# meroTV.net
KiCad netlist of a schematic drawn in EAGLE
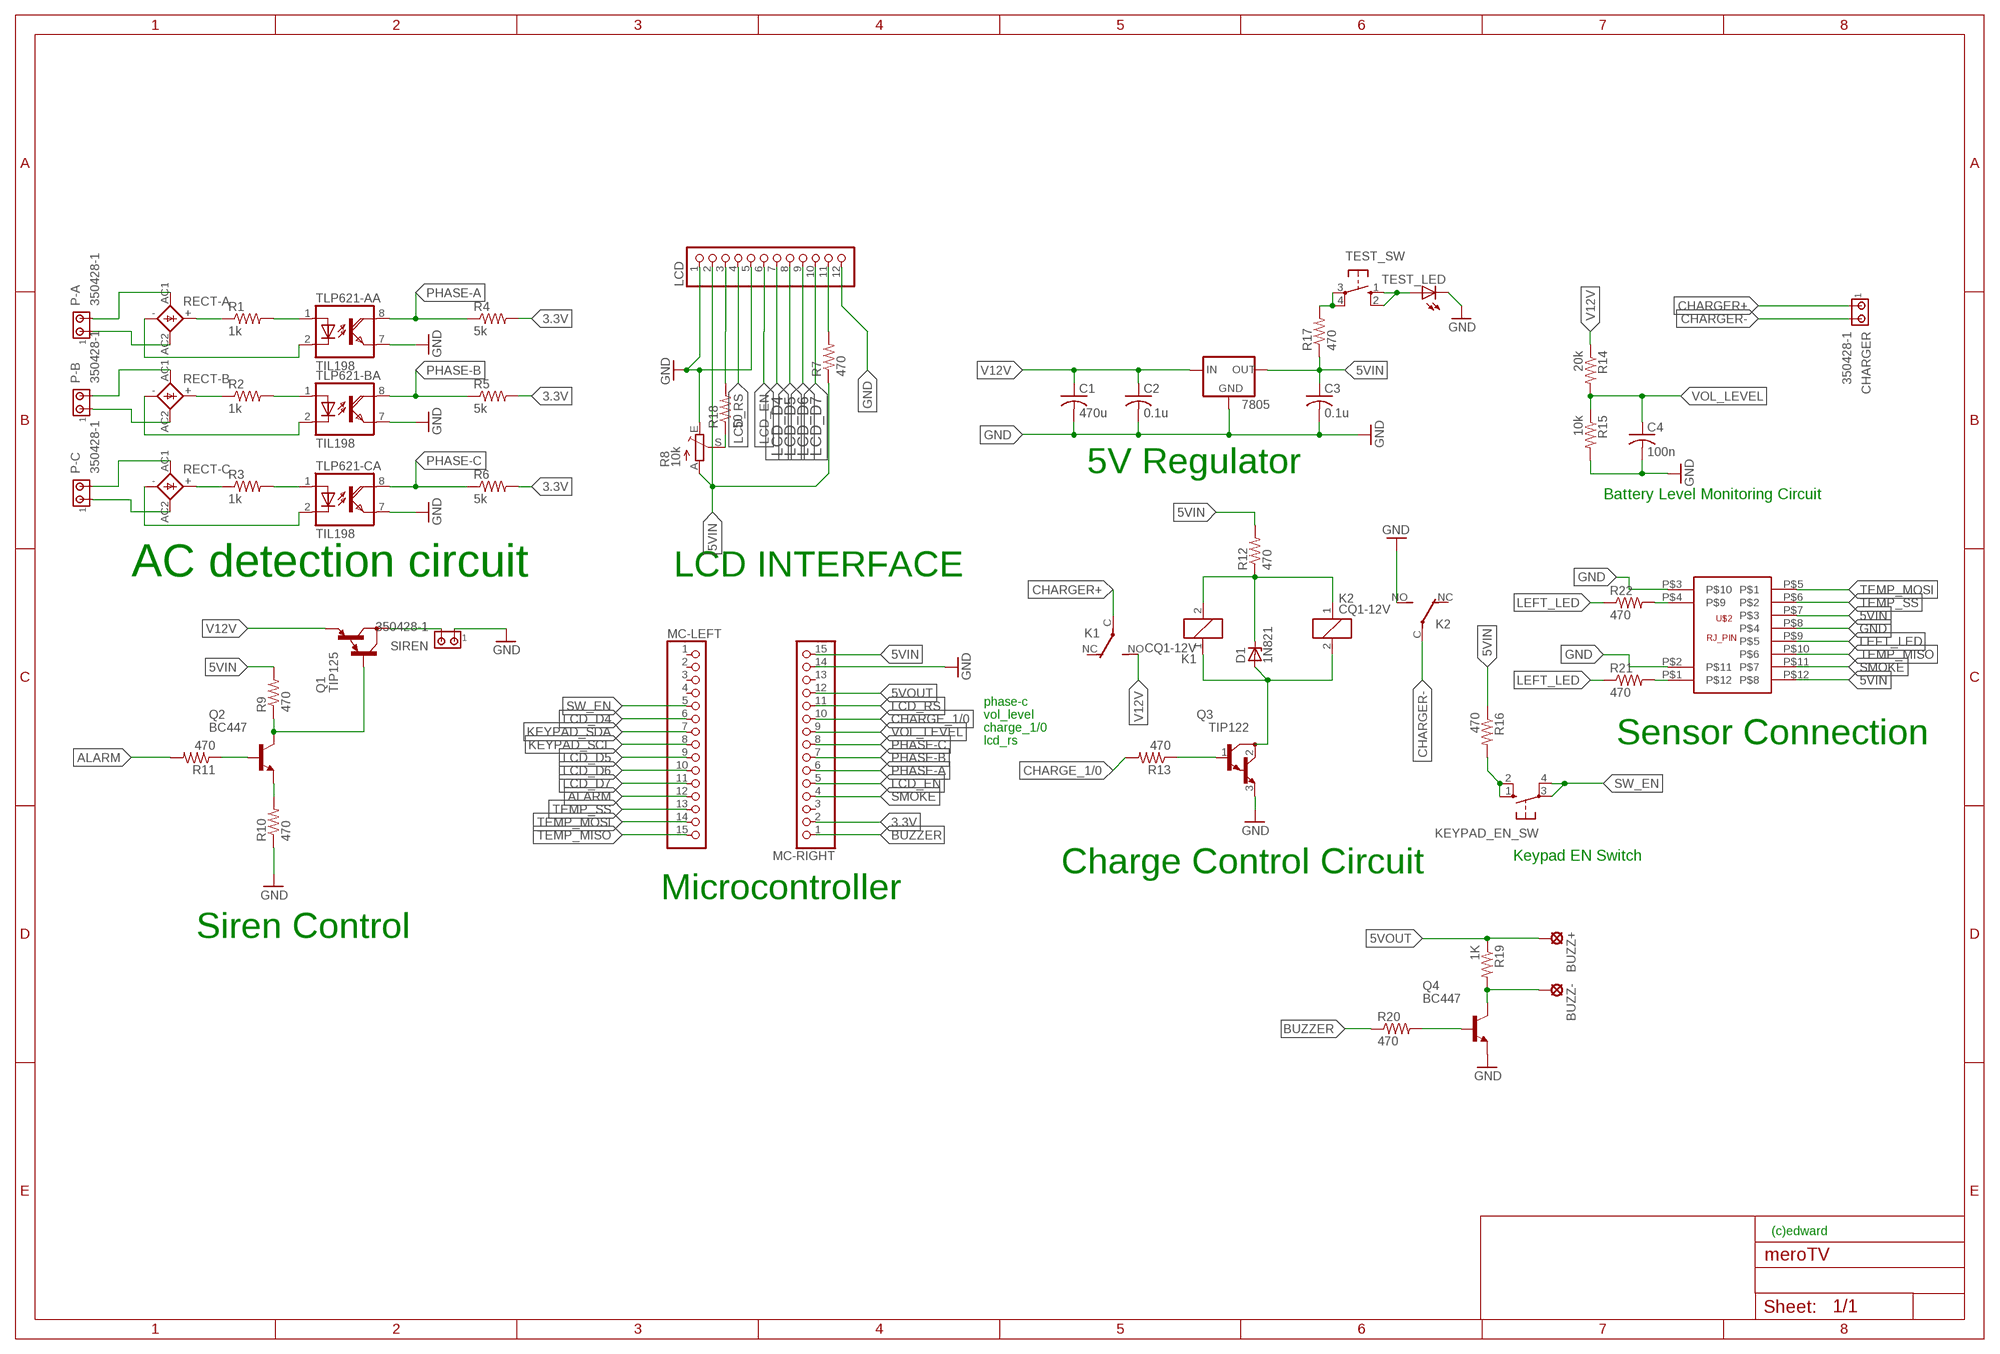
[diagram p0: schematic, sheet 1]

(export (version "E")
  (design (tool "Eeschema 10.0.6"))
  (components
    (comp (ref "7805")
      (value "78MXXL")
      (footprint "eagle-import:78MXXL")
      (libsource (lib "eagle-import") (part "78MXXL"))
    )
    (comp (ref "BUZZ+")
      (value "SE11")
      (footprint "eagle-import:SE11")
      (libsource (lib "eagle-import") (part "SE11"))
    )
    (comp (ref "BUZZ-")
      (value "SE11")
      (footprint "eagle-import:SE11")
      (libsource (lib "eagle-import") (part "SE11"))
    )
    (comp (ref "C1")
      (value "470u")
      (footprint "eagle-import:C025-040X050")
      (libsource (lib "eagle-import") (part "C-US025-040X050"))
    )
    (comp (ref "C2")
      (value "0.1u")
      (footprint "eagle-import:C025-030X050")
      (libsource (lib "eagle-import") (part "C-US025-030X050"))
    )
    (comp (ref "C3")
      (value "0.1u")
      (footprint "eagle-import:C025-030X050")
      (libsource (lib "eagle-import") (part "C-US025-030X050"))
    )
    (comp (ref "C4")
      (value "100n")
      (footprint "eagle-import:C025-030X050")
      (libsource (lib "eagle-import") (part "C-US025-030X050"))
    )
    (comp (ref "CHARGER")
      (value "350428-1")
      (footprint "eagle-import:350428-1")
      (libsource (lib "eagle-import") (part "350428-1"))
    )
    (comp (ref "D1")
      (value "1N821")
      (footprint "eagle-import:DO35Z10")
      (libsource (lib "eagle-import") (part "1N821"))
    )
    (comp (ref "K1")
      (value "CQ1-12V")
      (footprint "eagle-import:CQ1")
      (libsource (lib "eagle-import") (part "CQ1-12V"))
    )
    (comp (ref "K2")
      (value "CQ1-12V")
      (footprint "eagle-import:CQ1")
      (libsource (lib "eagle-import") (part "CQ1-12V"))
    )
    (comp (ref "KEYPAD_EN_SW")
      (value "10-XX")
      (footprint "eagle-import:B3F-10XX")
      (fields (field (name "MPN") "B3F-1000"))
      (libsource (lib "eagle-import") (part "10-XX"))
    )
    (comp (ref "LCD")
      (value "PINHD-1X12")
      (footprint "eagle-import:1X12")
      (libsource (lib "eagle-import") (part "PINHD-1X12"))
    )
    (comp (ref "MC-LEFT")
      (value "PINHD-1X15")
      (footprint "eagle-import:1X15")
      (libsource (lib "eagle-import") (part "PINHD-1X15"))
    )
    (comp (ref "MC-RIGHT")
      (value "PINHD-1X15")
      (footprint "eagle-import:1X15")
      (libsource (lib "eagle-import") (part "PINHD-1X15"))
    )
    (comp (ref "P-A")
      (value "350428-1")
      (footprint "eagle-import:350428-1")
      (libsource (lib "eagle-import") (part "350428-1"))
    )
    (comp (ref "P-B")
      (value "350428-1")
      (footprint "eagle-import:350428-1")
      (libsource (lib "eagle-import") (part "350428-1"))
    )
    (comp (ref "P-C")
      (value "350428-1")
      (footprint "eagle-import:350428-1")
      (libsource (lib "eagle-import") (part "350428-1"))
    )
    (comp (ref "Q1")
      (value "TIP125")
      (footprint "eagle-import:TO220")
      (libsource (lib "eagle-import") (part "TIP125"))
    )
    (comp (ref "Q2")
      (value "BC447")
      (footprint "eagle-import:TO92-EBC")
      (libsource (lib "eagle-import") (part "BC447"))
    )
    (comp (ref "Q3")
      (value "TIP122")
      (footprint "eagle-import:TO220")
      (libsource (lib "eagle-import") (part "TIP122"))
    )
    (comp (ref "Q4")
      (value "BC447")
      (footprint "eagle-import:TO92-EBC")
      (libsource (lib "eagle-import") (part "BC447"))
    )
    (comp (ref "R1")
      (value "1k")
      (footprint "eagle-import:0204_5")
      (libsource (lib "eagle-import") (part "R-US_0204/5"))
    )
    (comp (ref "R2")
      (value "1k")
      (footprint "eagle-import:0204_5")
      (libsource (lib "eagle-import") (part "R-US_0204/5"))
    )
    (comp (ref "R3")
      (value "1k")
      (footprint "eagle-import:0204_5")
      (libsource (lib "eagle-import") (part "R-US_0204/5"))
    )
    (comp (ref "R4")
      (value "5k")
      (footprint "eagle-import:0204_5")
      (libsource (lib "eagle-import") (part "R-US_0204/5"))
    )
    (comp (ref "R5")
      (value "5k")
      (footprint "eagle-import:0204_5")
      (libsource (lib "eagle-import") (part "R-US_0204/5"))
    )
    (comp (ref "R6")
      (value "5k")
      (footprint "eagle-import:0204_5")
      (libsource (lib "eagle-import") (part "R-US_0204/5"))
    )
    (comp (ref "R7")
      (value "470")
      (footprint "eagle-import:0204_5")
      (libsource (lib "eagle-import") (part "R-US_0204/5"))
    )
    (comp (ref "R8")
      (value "10k")
      (footprint "eagle-import:B25V")
      (libsource (lib "eagle-import") (part "TRIM_EU-B25V"))
    )
    (comp (ref "R9")
      (value "470")
      (footprint "eagle-import:0204_5")
      (libsource (lib "eagle-import") (part "R-US_0204/5"))
    )
    (comp (ref "R10")
      (value "470")
      (footprint "eagle-import:0204_5")
      (libsource (lib "eagle-import") (part "R-US_0204/5"))
    )
    (comp (ref "R11")
      (value "470")
      (footprint "eagle-import:0204_5")
      (libsource (lib "eagle-import") (part "R-US_0204/5"))
    )
    (comp (ref "R12")
      (value "470")
      (footprint "eagle-import:0204_5")
      (libsource (lib "eagle-import") (part "R-US_0204/5"))
    )
    (comp (ref "R13")
      (value "470")
      (footprint "eagle-import:0204_5")
      (libsource (lib "eagle-import") (part "R-US_0204/5"))
    )
    (comp (ref "R14")
      (value "20k")
      (footprint "eagle-import:0204_5")
      (libsource (lib "eagle-import") (part "R-US_0204/5"))
    )
    (comp (ref "R15")
      (value "10k")
      (footprint "eagle-import:0204_5")
      (libsource (lib "eagle-import") (part "R-US_0204/5"))
    )
    (comp (ref "R16")
      (value "470")
      (footprint "eagle-import:0204_5")
      (libsource (lib "eagle-import") (part "R-US_0204/5"))
    )
    (comp (ref "R17")
      (value "470")
      (footprint "eagle-import:0204_5")
      (libsource (lib "eagle-import") (part "R-US_0204/5"))
    )
    (comp (ref "R18")
      (value "50")
      (footprint "eagle-import:0204_5")
      (libsource (lib "eagle-import") (part "R-US_0204/5"))
    )
    (comp (ref "R19")
      (value "1K")
      (footprint "eagle-import:0204_5")
      (libsource (lib "eagle-import") (part "R-US_0204/5"))
    )
    (comp (ref "R20")
      (value "470")
      (footprint "eagle-import:0204_5")
      (libsource (lib "eagle-import") (part "R-US_0204/5"))
    )
    (comp (ref "R21")
      (value "470")
      (footprint "eagle-import:0204_5")
      (libsource (lib "eagle-import") (part "R-US_0204/5"))
    )
    (comp (ref "R22")
      (value "470")
      (footprint "eagle-import:0204_5")
      (libsource (lib "eagle-import") (part "R-US_0204/5"))
    )
    (comp (ref "RECT-A")
      (value "2KBB-R")
      (footprint "eagle-import:2KBB-R")
      (libsource (lib "eagle-import") (part "2KBB-R"))
    )
    (comp (ref "RECT-B")
      (value "2KBB-R")
      (footprint "eagle-import:2KBB-R")
      (libsource (lib "eagle-import") (part "2KBB-R"))
    )
    (comp (ref "RECT-C")
      (value "2KBB-R")
      (footprint "eagle-import:2KBB-R")
      (libsource (lib "eagle-import") (part "2KBB-R"))
    )
    (comp (ref "SIREN")
      (value "350428-1")
      (footprint "eagle-import:350428-1")
      (libsource (lib "eagle-import") (part "350428-1"))
    )
    (comp (ref "TEST_LED")
      (value "LED3MM")
      (footprint "eagle-import:LED3MM")
      (libsource (lib "eagle-import") (part "LED3MM"))
    )
    (comp (ref "TEST_SW")
      (value "10-XX")
      (footprint "eagle-import:B3F-10XX")
      (fields (field (name "MPN") "B3F-1000"))
      (libsource (lib "eagle-import") (part "10-XX"))
    )
    (comp (ref "TLP621-A")
      (value "TIL198")
      (footprint "eagle-import:DIL08")
      (libsource (lib "eagle-import") (part "TIL198"))
    )
    (comp (ref "TLP621-B")
      (value "TIL198")
      (footprint "eagle-import:DIL08")
      (libsource (lib "eagle-import") (part "TIL198"))
    )
    (comp (ref "TLP621-C")
      (value "TIL198")
      (footprint "eagle-import:DIL08")
      (libsource (lib "eagle-import") (part "TIL198"))
    )
    (comp (ref "U$2")
      (value "RJ45_EDWRJ45-DIL")
      (footprint "eagle-import:RJ45-DIL")
      (libsource (lib "eagle-import") (part "RJ45_EDWRJ45-DIL"))
    )
  )
  (nets
    (net (code "1") (name "3.3V") (class "Default")
      (node (ref "MC-RIGHT") (pin "2") (pinfunction "2_2") (pintype "passive"))
      (node (ref "R4") (pin "2") (pinfunction "2_2") (pintype "passive"))
      (node (ref "R5") (pin "2") (pinfunction "2_2") (pintype "passive"))
      (node (ref "R6") (pin "2") (pinfunction "2_2") (pintype "passive"))
    )
    (net (code "2") (name "5VIN") (class "Default")
      (node (ref "7805") (pin "OUT") (pinfunction "OUT_OUT") (pintype "passive"))
      (node (ref "C3") (pin "1") (pinfunction "1_1") (pintype "passive"))
      (node (ref "LCD") (pin "2") (pinfunction "2_2") (pintype "passive"))
      (node (ref "MC-RIGHT") (pin "15") (pinfunction "15_15") (pintype "passive"))
      (node (ref "R12") (pin "2") (pinfunction "2_2") (pintype "passive"))
      (node (ref "R16") (pin "1") (pinfunction "1_1") (pintype "passive"))
      (node (ref "R17") (pin "1") (pinfunction "1_1") (pintype "passive"))
      (node (ref "R7") (pin "1") (pinfunction "1_1") (pintype "passive"))
      (node (ref "R8") (pin "A") (pinfunction "A_A") (pintype "passive"))
      (node (ref "R9") (pin "2") (pinfunction "2_2") (pintype "passive"))
      (node (ref "U$2") (pin "P$12") (pinfunction "P$8_P$12") (pintype "bidirectional"))
      (node (ref "U$2") (pin "P$7") (pinfunction "P$3_P$7") (pintype "bidirectional"))
    )
    (net (code "3") (name "5VOUT") (class "Default")
      (node (ref "BUZZ+") (pin "MP") (pinfunction "MP_MP") (pintype "passive"))
      (node (ref "MC-RIGHT") (pin "12") (pinfunction "12_12") (pintype "passive"))
      (node (ref "R19") (pin "1") (pinfunction "1_1") (pintype "passive"))
    )
    (net (code "4") (name "ALARM") (class "Default")
      (node (ref "MC-LEFT") (pin "12") (pinfunction "12_12") (pintype "passive"))
      (node (ref "R11") (pin "2") (pinfunction "2_2") (pintype "passive"))
    )
    (net (code "5") (name "BUZZER") (class "Default")
      (node (ref "MC-RIGHT") (pin "1") (pinfunction "1_1") (pintype "passive"))
      (node (ref "R20") (pin "1") (pinfunction "1_1") (pintype "passive"))
    )
    (net (code "6") (name "CHARGER+") (class "Default")
      (node (ref "CHARGER") (pin "1") (pinfunction "1_1") (pintype "passive"))
      (node (ref "K1") (pin "C") (pinfunction "P_C") (pintype "passive"))
    )
    (net (code "7") (name "CHARGER-") (class "Default")
      (node (ref "CHARGER") (pin "2") (pinfunction "2_2") (pintype "passive"))
      (node (ref "K2") (pin "C") (pinfunction "P_C") (pintype "passive"))
    )
    (net (code "8") (name "CHARGE_1{slash}0") (class "Default")
      (node (ref "MC-RIGHT") (pin "10") (pinfunction "10_10") (pintype "passive"))
      (node (ref "R13") (pin "2") (pinfunction "2_2") (pintype "passive"))
    )
    (net (code "9") (name "GND") (class "Default")
      (node (ref "7805") (pin "GND") (pinfunction "GND_GND") (pintype "input"))
      (node (ref "C1") (pin "2") (pinfunction "2_2") (pintype "passive"))
      (node (ref "C2") (pin "2") (pinfunction "2_2") (pintype "passive"))
      (node (ref "C3") (pin "2") (pinfunction "2_2") (pintype "passive"))
      (node (ref "C4") (pin "2") (pinfunction "2_2") (pintype "passive"))
      (node (ref "K2") (pin "NO") (pinfunction "S_NO") (pintype "passive"))
      (node (ref "LCD") (pin "1") (pinfunction "1_1") (pintype "passive"))
      (node (ref "LCD") (pin "12") (pinfunction "12_12") (pintype "passive"))
      (node (ref "LCD") (pin "5") (pinfunction "5_5") (pintype "passive"))
      (node (ref "MC-RIGHT") (pin "14") (pinfunction "14_14") (pintype "passive"))
      (node (ref "Q3") (pin "3") (pinfunction "E_3") (pintype "passive"))
      (node (ref "Q4") (pin "E") (pinfunction "E_E") (pintype "passive"))
      (node (ref "R10") (pin "1") (pinfunction "1_1") (pintype "passive"))
      (node (ref "R15") (pin "2") (pinfunction "2_2") (pintype "passive"))
      (node (ref "R8") (pin "E") (pinfunction "E_E") (pintype "passive"))
      (node (ref "SIREN") (pin "1") (pinfunction "1_1") (pintype "passive"))
      (node (ref "TEST_LED") (pin "K") (pinfunction "C_K") (pintype "passive"))
      (node (ref "TLP621-A") (pin "7") (pinfunction "EMI_7") (pintype "passive"))
      (node (ref "TLP621-B") (pin "7") (pinfunction "EMI_7") (pintype "passive"))
      (node (ref "TLP621-C") (pin "7") (pinfunction "EMI_7") (pintype "passive"))
      (node (ref "U$2") (pin "P$2") (pinfunction "P$11_P$2") (pintype "bidirectional"))
      (node (ref "U$2") (pin "P$3") (pinfunction "P$10_P$3") (pintype "bidirectional"))
      (node (ref "U$2") (pin "P$8") (pinfunction "P$4_P$8") (pintype "bidirectional"))
    )
    (net (code "10") (name "KEYPAD_SCL") (class "Default")
      (node (ref "MC-LEFT") (pin "8") (pinfunction "8_8") (pintype "passive"))
    )
    (net (code "11") (name "KEYPAD_SDA") (class "Default")
      (node (ref "MC-LEFT") (pin "7") (pinfunction "7_7") (pintype "passive"))
    )
    (net (code "12") (name "LCD_D4") (class "Default")
      (node (ref "LCD") (pin "7") (pinfunction "7_7") (pintype "passive"))
      (node (ref "MC-LEFT") (pin "6") (pinfunction "6_6") (pintype "passive"))
    )
    (net (code "13") (name "LCD_D5") (class "Default")
      (node (ref "LCD") (pin "8") (pinfunction "8_8") (pintype "passive"))
      (node (ref "MC-LEFT") (pin "9") (pinfunction "9_9") (pintype "passive"))
    )
    (net (code "14") (name "LCD_D6") (class "Default")
      (node (ref "LCD") (pin "9") (pinfunction "9_9") (pintype "passive"))
      (node (ref "MC-LEFT") (pin "10") (pinfunction "10_10") (pintype "passive"))
    )
    (net (code "15") (name "LCD_D7") (class "Default")
      (node (ref "LCD") (pin "10") (pinfunction "10_10") (pintype "passive"))
      (node (ref "MC-LEFT") (pin "11") (pinfunction "11_11") (pintype "passive"))
    )
    (net (code "16") (name "LCD_EN") (class "Default")
      (node (ref "LCD") (pin "6") (pinfunction "6_6") (pintype "passive"))
      (node (ref "MC-RIGHT") (pin "5") (pinfunction "5_5") (pintype "passive"))
    )
    (net (code "17") (name "LCD_RS") (class "Default")
      (node (ref "LCD") (pin "4") (pinfunction "4_4") (pintype "passive"))
      (node (ref "MC-RIGHT") (pin "11") (pinfunction "11_11") (pintype "passive"))
    )
    (net (code "18") (name "LEFT_LED") (class "Default")
      (node (ref "R21") (pin "1") (pinfunction "1_1") (pintype "passive"))
      (node (ref "R22") (pin "1") (pinfunction "1_1") (pintype "passive"))
      (node (ref "U$2") (pin "P$9") (pinfunction "P$5_P$9") (pintype "bidirectional"))
    )
    (net (code "19") (name "Net-(BUZZ--PadMP)") (class "Default")
      (node (ref "BUZZ-") (pin "MP") (pinfunction "MP_MP") (pintype "passive"))
      (node (ref "Q4") (pin "C") (pinfunction "C_C") (pintype "passive"))
      (node (ref "R19") (pin "2") (pinfunction "2_2") (pintype "passive"))
    )
    (net (code "20") (name "Net-(D1-PadC)") (class "Default")
      (node (ref "D1") (pin "C") (pinfunction "C_C") (pintype "passive"))
      (node (ref "K1") (pin "2") (pinfunction "2_2") (pintype "passive"))
      (node (ref "K2") (pin "1") (pinfunction "1_1") (pintype "passive"))
      (node (ref "R12") (pin "1") (pinfunction "1_1") (pintype "passive"))
    )
    (net (code "21") (name "Net-(KEYPAD_EN_SW-S)") (class "Default")
      (node (ref "KEYPAD_EN_SW") (pin "1") (pinfunction "S_1") (pintype "passive"))
      (node (ref "KEYPAD_EN_SW") (pin "2") (pinfunction "S1_2") (pintype "passive"))
      (node (ref "R16") (pin "2") (pinfunction "2_2") (pintype "passive"))
    )
    (net (code "22") (name "Net-(LCD-Pad3)") (class "Default")
      (node (ref "LCD") (pin "3") (pinfunction "3_3") (pintype "passive"))
      (node (ref "R18") (pin "2") (pinfunction "2_2") (pintype "passive"))
    )
    (net (code "23") (name "Net-(LCD-Pad11)") (class "Default")
      (node (ref "LCD") (pin "11") (pinfunction "11_11") (pintype "passive"))
      (node (ref "R7") (pin "2") (pinfunction "2_2") (pintype "passive"))
    )
    (net (code "24") (name "Net-(P-A-Pad1)") (class "Default")
      (node (ref "P-A") (pin "1") (pinfunction "1_1") (pintype "passive"))
      (node (ref "RECT-A") (pin "AC2") (pinfunction "AC2_AC2") (pintype "passive"))
    )
    (net (code "25") (name "Net-(P-A-Pad2)") (class "Default")
      (node (ref "P-A") (pin "2") (pinfunction "2_2") (pintype "passive"))
      (node (ref "RECT-A") (pin "AC1") (pinfunction "AC1_AC1") (pintype "passive"))
    )
    (net (code "26") (name "Net-(P-B-Pad1)") (class "Default")
      (node (ref "P-B") (pin "1") (pinfunction "1_1") (pintype "passive"))
      (node (ref "RECT-B") (pin "AC2") (pinfunction "AC2_AC2") (pintype "passive"))
    )
    (net (code "27") (name "Net-(P-B-Pad2)") (class "Default")
      (node (ref "P-B") (pin "2") (pinfunction "2_2") (pintype "passive"))
      (node (ref "RECT-B") (pin "AC1") (pinfunction "AC1_AC1") (pintype "passive"))
    )
    (net (code "28") (name "Net-(P-C-Pad1)") (class "Default")
      (node (ref "P-C") (pin "1") (pinfunction "1_1") (pintype "passive"))
      (node (ref "RECT-C") (pin "AC2") (pinfunction "AC2_AC2") (pintype "passive"))
    )
    (net (code "29") (name "Net-(P-C-Pad2)") (class "Default")
      (node (ref "P-C") (pin "2") (pinfunction "2_2") (pintype "passive"))
      (node (ref "RECT-C") (pin "AC1") (pinfunction "AC1_AC1") (pintype "passive"))
    )
    (net (code "30") (name "Net-(Q1-B)") (class "Default")
      (node (ref "Q1") (pin "1") (pinfunction "B_1") (pintype "passive"))
      (node (ref "Q2") (pin "C") (pinfunction "C_C") (pintype "passive"))
      (node (ref "R9") (pin "1") (pinfunction "1_1") (pintype "passive"))
    )
    (net (code "31") (name "Net-(Q1-C)") (class "Default")
      (node (ref "Q1") (pin "2") (pinfunction "C_2") (pintype "passive"))
      (node (ref "SIREN") (pin "2") (pinfunction "2_2") (pintype "passive"))
    )
    (net (code "32") (name "Net-(Q2-PadB)") (class "Default")
      (node (ref "Q2") (pin "B") (pinfunction "B_B") (pintype "passive"))
      (node (ref "R11") (pin "1") (pinfunction "1_1") (pintype "passive"))
    )
    (net (code "33") (name "Net-(Q2-PadE)") (class "Default")
      (node (ref "Q2") (pin "E") (pinfunction "E_E") (pintype "passive"))
      (node (ref "R10") (pin "2") (pinfunction "2_2") (pintype "passive"))
    )
    (net (code "34") (name "Net-(Q3-B)") (class "Default")
      (node (ref "Q3") (pin "1") (pinfunction "B_1") (pintype "passive"))
      (node (ref "R13") (pin "1") (pinfunction "1_1") (pintype "passive"))
    )
    (net (code "35") (name "Net-(Q3-C)") (class "Default")
      (node (ref "D1") (pin "A") (pinfunction "A_A") (pintype "passive"))
      (node (ref "K1") (pin "1") (pinfunction "1_1") (pintype "passive"))
      (node (ref "K2") (pin "2") (pinfunction "2_2") (pintype "passive"))
      (node (ref "Q3") (pin "2") (pinfunction "C_2") (pintype "passive"))
    )
    (net (code "36") (name "Net-(Q4-PadB)") (class "Default")
      (node (ref "Q4") (pin "B") (pinfunction "B_B") (pintype "passive"))
      (node (ref "R20") (pin "2") (pinfunction "2_2") (pintype "passive"))
    )
    (net (code "37") (name "Net-(R1-Pad1)") (class "Default")
      (node (ref "R1") (pin "1") (pinfunction "1_1") (pintype "passive"))
      (node (ref "RECT-A") (pin "+") (pinfunction "+_+") (pintype "passive"))
    )
    (net (code "38") (name "Net-(R2-Pad1)") (class "Default")
      (node (ref "R2") (pin "1") (pinfunction "1_1") (pintype "passive"))
      (node (ref "RECT-B") (pin "+") (pinfunction "+_+") (pintype "passive"))
    )
    (net (code "39") (name "Net-(R3-Pad1)") (class "Default")
      (node (ref "R3") (pin "1") (pinfunction "1_1") (pintype "passive"))
      (node (ref "RECT-C") (pin "+") (pinfunction "+_+") (pintype "passive"))
    )
    (net (code "40") (name "Net-(R18-Pad1)") (class "Default")
      (node (ref "R18") (pin "1") (pinfunction "1_1") (pintype "passive"))
      (node (ref "R8") (pin "S") (pinfunction "S_S") (pintype "passive"))
    )
    (net (code "41") (name "Net-(TEST_SW-P)") (class "Default")
      (node (ref "R17") (pin "2") (pinfunction "2_2") (pintype "passive"))
      (node (ref "TEST_SW") (pin "3") (pinfunction "P_3") (pintype "passive"))
      (node (ref "TEST_SW") (pin "4") (pinfunction "P1_4") (pintype "passive"))
    )
    (net (code "42") (name "Net-(TEST_SW-S)") (class "Default")
      (node (ref "TEST_LED") (pin "A") (pinfunction "A_A") (pintype "passive"))
      (node (ref "TEST_SW") (pin "1") (pinfunction "S_1") (pintype "passive"))
      (node (ref "TEST_SW") (pin "2") (pinfunction "S1_2") (pintype "passive"))
    )
    (net (code "43") (name "Net-(TLP621-AA-A)") (class "Default")
      (node (ref "R1") (pin "2") (pinfunction "2_2") (pintype "passive"))
      (node (ref "TLP621-A") (pin "1") (pinfunction "A_1") (pintype "passive"))
    )
    (net (code "44") (name "Net-(TLP621-AA-C)") (class "Default")
      (node (ref "RECT-A") (pin "-") (pinfunction "-_-") (pintype "passive"))
      (node (ref "TLP621-A") (pin "2") (pinfunction "C_2") (pintype "passive"))
    )
    (net (code "45") (name "Net-(TLP621-BA-A)") (class "Default")
      (node (ref "R2") (pin "2") (pinfunction "2_2") (pintype "passive"))
      (node (ref "TLP621-B") (pin "1") (pinfunction "A_1") (pintype "passive"))
    )
    (net (code "46") (name "Net-(TLP621-BA-C)") (class "Default")
      (node (ref "RECT-B") (pin "-") (pinfunction "-_-") (pintype "passive"))
      (node (ref "TLP621-B") (pin "2") (pinfunction "C_2") (pintype "passive"))
    )
    (net (code "47") (name "Net-(TLP621-CA-A)") (class "Default")
      (node (ref "R3") (pin "2") (pinfunction "2_2") (pintype "passive"))
      (node (ref "TLP621-C") (pin "1") (pinfunction "A_1") (pintype "passive"))
    )
    (net (code "48") (name "Net-(TLP621-CA-C)") (class "Default")
      (node (ref "RECT-C") (pin "-") (pinfunction "-_-") (pintype "passive"))
      (node (ref "TLP621-C") (pin "2") (pinfunction "C_2") (pintype "passive"))
    )
    (net (code "49") (name "Net-(U$2-P$9)") (class "Default")
      (node (ref "R22") (pin "2") (pinfunction "2_2") (pintype "passive"))
      (node (ref "U$2") (pin "P$4") (pinfunction "P$9_P$4") (pintype "bidirectional"))
    )
    (net (code "50") (name "Net-(U$2-P$12)") (class "Default")
      (node (ref "R21") (pin "2") (pinfunction "2_2") (pintype "passive"))
      (node (ref "U$2") (pin "P$1") (pinfunction "P$12_P$1") (pintype "bidirectional"))
    )
    (net (code "51") (name "PHASE-A") (class "Default")
      (node (ref "MC-RIGHT") (pin "6") (pinfunction "6_6") (pintype "passive"))
      (node (ref "R4") (pin "1") (pinfunction "1_1") (pintype "passive"))
      (node (ref "TLP621-A") (pin "8") (pinfunction "COL_8") (pintype "passive"))
    )
    (net (code "52") (name "PHASE-B") (class "Default")
      (node (ref "MC-RIGHT") (pin "7") (pinfunction "7_7") (pintype "passive"))
      (node (ref "R5") (pin "1") (pinfunction "1_1") (pintype "passive"))
      (node (ref "TLP621-B") (pin "8") (pinfunction "COL_8") (pintype "passive"))
    )
    (net (code "53") (name "PHASE-C") (class "Default")
      (node (ref "MC-RIGHT") (pin "8") (pinfunction "8_8") (pintype "passive"))
      (node (ref "R6") (pin "1") (pinfunction "1_1") (pintype "passive"))
      (node (ref "TLP621-C") (pin "8") (pinfunction "COL_8") (pintype "passive"))
    )
    (net (code "54") (name "SMOKE") (class "Default")
      (node (ref "MC-RIGHT") (pin "4") (pinfunction "4_4") (pintype "passive"))
      (node (ref "U$2") (pin "P$11") (pinfunction "P$7_P$11") (pintype "bidirectional"))
    )
    (net (code "55") (name "SW_EN") (class "Default")
      (node (ref "KEYPAD_EN_SW") (pin "3") (pinfunction "P_3") (pintype "passive"))
      (node (ref "KEYPAD_EN_SW") (pin "4") (pinfunction "P1_4") (pintype "passive"))
      (node (ref "MC-LEFT") (pin "5") (pinfunction "5_5") (pintype "passive"))
    )
    (net (code "56") (name "TEMP_MISO") (class "Default")
      (node (ref "MC-LEFT") (pin "15") (pinfunction "15_15") (pintype "passive"))
      (node (ref "U$2") (pin "P$10") (pinfunction "P$6_P$10") (pintype "bidirectional"))
    )
    (net (code "57") (name "TEMP_MOSI") (class "Default")
      (node (ref "MC-LEFT") (pin "14") (pinfunction "14_14") (pintype "passive"))
      (node (ref "U$2") (pin "P$5") (pinfunction "P$1_P$5") (pintype "bidirectional"))
    )
    (net (code "58") (name "TEMP_SS") (class "Default")
      (node (ref "MC-LEFT") (pin "13") (pinfunction "13_13") (pintype "passive"))
      (node (ref "U$2") (pin "P$6") (pinfunction "P$2_P$6") (pintype "bidirectional"))
    )
    (net (code "59") (name "V12V") (class "Default")
      (node (ref "7805") (pin "IN") (pinfunction "IN_IN") (pintype "input"))
      (node (ref "C1") (pin "1") (pinfunction "1_1") (pintype "passive"))
      (node (ref "C2") (pin "1") (pinfunction "1_1") (pintype "passive"))
      (node (ref "K1") (pin "NO") (pinfunction "S_NO") (pintype "passive"))
      (node (ref "Q1") (pin "3") (pinfunction "E_3") (pintype "passive"))
      (node (ref "R14") (pin "1") (pinfunction "1_1") (pintype "passive"))
    )
    (net (code "60") (name "VOL_LEVEL") (class "Default")
      (node (ref "C4") (pin "1") (pinfunction "1_1") (pintype "passive"))
      (node (ref "MC-RIGHT") (pin "9") (pinfunction "9_9") (pintype "passive"))
      (node (ref "R14") (pin "2") (pinfunction "2_2") (pintype "passive"))
      (node (ref "R15") (pin "1") (pinfunction "1_1") (pintype "passive"))
    )
    (net (code "61") (name "unconnected-(K1B-O-PadNC)") (class "Default")
      (node (ref "K1") (pin "NC") (pinfunction "O_NC") (pintype "passive"))
    )
    (net (code "62") (name "unconnected-(K2B-O-PadNC)") (class "Default")
      (node (ref "K2") (pin "NC") (pinfunction "O_NC") (pintype "passive"))
    )
    (net (code "63") (name "unconnected-(MC-LEFT-Pad1)") (class "Default")
      (node (ref "MC-LEFT") (pin "1") (pinfunction "1_1") (pintype "passive"))
    )
    (net (code "64") (name "unconnected-(MC-LEFT-Pad2)") (class "Default")
      (node (ref "MC-LEFT") (pin "2") (pinfunction "2_2") (pintype "passive"))
    )
    (net (code "65") (name "unconnected-(MC-LEFT-Pad3)") (class "Default")
      (node (ref "MC-LEFT") (pin "3") (pinfunction "3_3") (pintype "passive"))
    )
    (net (code "66") (name "unconnected-(MC-LEFT-Pad4)") (class "Default")
      (node (ref "MC-LEFT") (pin "4") (pinfunction "4_4") (pintype "passive"))
    )
    (net (code "67") (name "unconnected-(MC-RIGHT-Pad3)") (class "Default")
      (node (ref "MC-RIGHT") (pin "3") (pinfunction "3_3") (pintype "passive"))
    )
    (net (code "68") (name "unconnected-(MC-RIGHT-Pad13)") (class "Default")
      (node (ref "MC-RIGHT") (pin "13") (pinfunction "13_13") (pintype "passive"))
    )
  )
)
